# GSM.net
KiCad netlist of a schematic drawn in Altium Designer
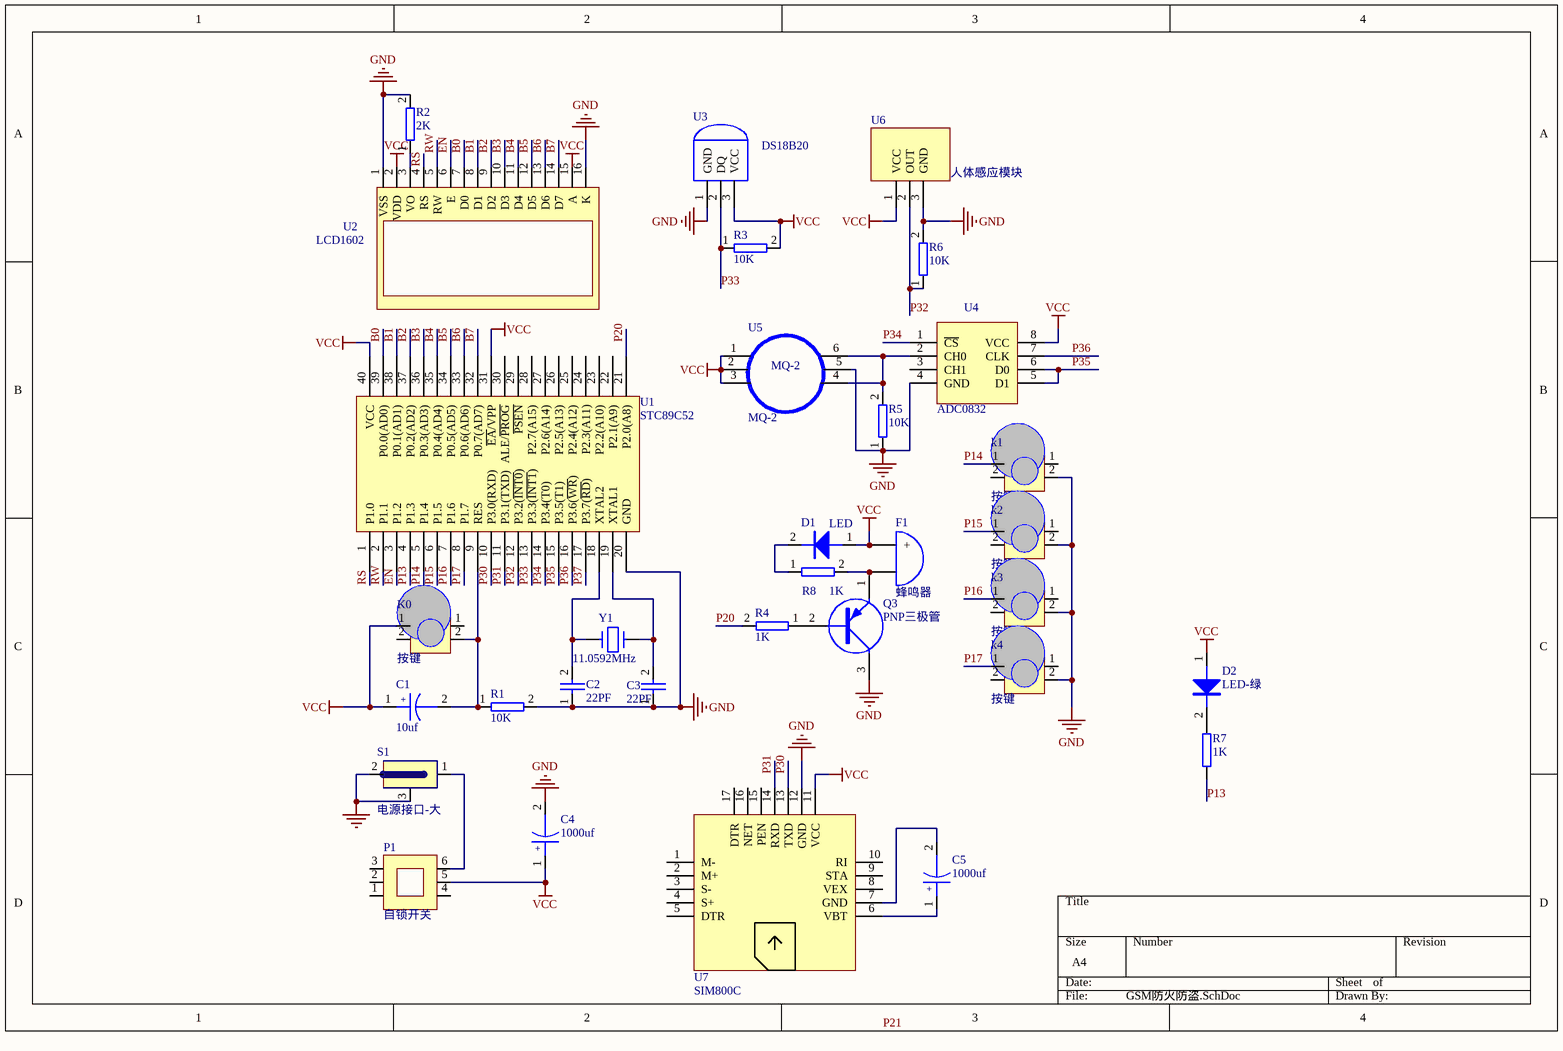
[diagram p0: GSM防火防盗.SchDoc]

(export (version "E")
  (design (tool "Eeschema 10.0.6"))
  (components
    (comp (ref "C1") (value "10uf") (footprint "电容-电解10UF") (libsource (lib "元件集成库") (part "电解电容")))
    (comp (ref "C2") (value "22PF") (footprint "电容-瓷片") (libsource (lib "元件集成库") (part "瓷片电容")))
    (comp (ref "C3") (value "22PF") (footprint "电容-瓷片") (libsource (lib "元件集成库") (part "瓷片电容")))
    (comp (ref "C4")
      (value "1000uf")
      (footprint "电容-电解1000UF - 25V")
      (libsource (lib "元件集成库") (part "电解电容-1000uf-25v"))
    )
    (comp (ref "C5")
      (value "1000uf")
      (footprint "电容-电解1000UF - 25V")
      (libsource (lib "元件集成库") (part "电解电容-1000uf-25v"))
    )
    (comp (ref "D1") (value "LED") (footprint "LED") (libsource (lib "元件集成库") (part "LED")))
    (comp (ref "D2") (value "LED-绿") (footprint "LED-5MM") (libsource (lib "元件集成库") (part "LED-5MM")))
    (comp (ref "F1") (value "蜂鸣器") (footprint "蜂鸣器") (libsource (lib "元件集成库") (part "蜂鸣器")))
    (comp (ref "K0") (value "按键") (footprint "按键") (libsource (lib "元件集成库") (part "按键")))
    (comp (ref "k1") (value "按键") (footprint "按键") (libsource (lib "元件集成库") (part "按键")))
    (comp (ref "k2") (value "按键") (footprint "按键") (libsource (lib "元件集成库") (part "按键")))
    (comp (ref "k3") (value "按键") (footprint "按键") (libsource (lib "元件集成库") (part "按键")))
    (comp (ref "k4") (value "按键") (footprint "按键") (libsource (lib "元件集成库") (part "按键")))
    (comp (ref "P1") (value "自锁开关") (footprint "自锁开关") (libsource (lib "元件集成库") (part "自锁开关")))
    (comp (ref "Q3") (value "PNP三极管") (footprint "三极管") (libsource (lib "元件集成库") (part "PNP三极管")))
    (comp (ref "R1") (value "10K") (footprint "电阻") (libsource (lib "") (part "电阻-定值_1")))
    (comp (ref "R2") (value "2K") (footprint "电阻") (libsource (lib "") (part "电阻-定值_1")))
    (comp (ref "R3") (value "10K") (footprint "电阻") (libsource (lib "") (part "电阻-定值_1")))
    (comp (ref "R4") (value "1K") (footprint "电阻") (libsource (lib "") (part "电阻-定值_1")))
    (comp (ref "R5") (value "10K") (footprint "电阻") (libsource (lib "") (part "电阻-定值_1")))
    (comp (ref "R6") (value "10K") (footprint "电阻") (libsource (lib "") (part "电阻-定值_1")))
    (comp (ref "R7") (value "1K") (footprint "电阻") (libsource (lib "元件集成库") (part "电阻-定值")))
    (comp (ref "R8") (value "1K") (footprint "电阻") (libsource (lib "") (part "电阻-定值_1")))
    (comp (ref "S1") (value "电源接口-大") (footprint "电源座-大") (libsource (lib "元件集成库") (part "电源接口-大")))
    (comp (ref "U1") (value "STC89C52") (footprint "底座40P") (libsource (lib "元件集成库") (part "STC89C52")))
    (comp (ref "U2") (value "LCD1602") (footprint "LCD1602") (libsource (lib "元件集成库") (part "LCD1602")))
    (comp (ref "U3") (value "DS18B20") (footprint "三极管") (libsource (lib "元件集成库") (part "DS18B20")))
    (comp (ref "U4") (value "ADC0832") (footprint "底座8P") (libsource (lib "元件集成库") (part "ADC0832")))
    (comp (ref "U5") (value "MQ-2") (footprint "MQ-2") (libsource (lib "元件集成库") (part "MQ-2")))
    (comp (ref "U6") (value "人体感应模块") (footprint "人体感应模块") (libsource (lib "元件集成库") (part "人体感应模块")))
    (comp (ref "U7") (value "SIM800C") (footprint "SIM800C") (libsource (lib "元件集成库") (part "SIM800C")))
    (comp (ref "Y1") (value "11.0592MHz") (footprint "晶振") (libsource (lib "元件集成库") (part "晶振")))
  )
  (nets
    (net (code "1") (name "/B0") (class "Default")
      (node (ref "U1") (pin "39") (pinfunction "P0.0(AD0)_39") (pintype "passive"))
      (node (ref "U2") (pin "7") (pinfunction "D0_7") (pintype "passive"))
    )
    (net (code "2") (name "/B1") (class "Default")
      (node (ref "U1") (pin "38") (pinfunction "P0.1(AD1)_38") (pintype "passive"))
      (node (ref "U2") (pin "8") (pinfunction "D1_8") (pintype "passive"))
    )
    (net (code "3") (name "/B2") (class "Default")
      (node (ref "U1") (pin "37") (pinfunction "P0.2(AD2)_37") (pintype "passive"))
      (node (ref "U2") (pin "9") (pinfunction "D2_9") (pintype "passive"))
    )
    (net (code "4") (name "/B3") (class "Default")
      (node (ref "U1") (pin "36") (pinfunction "P0.3(AD3)_36") (pintype "passive"))
      (node (ref "U2") (pin "10") (pinfunction "D3_10") (pintype "passive"))
    )
    (net (code "5") (name "/B4") (class "Default")
      (node (ref "U1") (pin "35") (pinfunction "P0.4(AD4)_35") (pintype "passive"))
      (node (ref "U2") (pin "11") (pinfunction "D4_11") (pintype "passive"))
    )
    (net (code "6") (name "/B5") (class "Default")
      (node (ref "U1") (pin "34") (pinfunction "P0.5(AD5)_34") (pintype "passive"))
      (node (ref "U2") (pin "12") (pinfunction "D5_12") (pintype "passive"))
    )
    (net (code "7") (name "/B6") (class "Default")
      (node (ref "U1") (pin "33") (pinfunction "P0.6(AD6)_33") (pintype "passive"))
      (node (ref "U2") (pin "13") (pinfunction "D6_13") (pintype "passive"))
    )
    (net (code "8") (name "/B7") (class "Default")
      (node (ref "U1") (pin "32") (pinfunction "P0.7(AD7)_32") (pintype "passive"))
      (node (ref "U2") (pin "14") (pinfunction "D7_14") (pintype "passive"))
    )
    (net (code "9") (name "/EN") (class "Default")
      (node (ref "U1") (pin "3") (pinfunction "P1.2_3") (pintype "passive"))
      (node (ref "U2") (pin "6") (pinfunction "E_6") (pintype "passive"))
    )
    (net (code "10") (name "/P13") (class "Default")
      (node (ref "R7") (pin "1") (pinfunction "1_1") (pintype "passive"))
      (node (ref "U1") (pin "4") (pinfunction "P1.3_4") (pintype "passive"))
    )
    (net (code "11") (name "/P14") (class "Default")
      (node (ref "U1") (pin "5") (pinfunction "P1.4_5") (pintype "passive"))
      (node (ref "k1") (pin "1") (pinfunction "1_1") (pintype "passive"))
    )
    (net (code "12") (name "/P15") (class "Default")
      (node (ref "U1") (pin "6") (pinfunction "P1.5_6") (pintype "passive"))
      (node (ref "k2") (pin "1") (pinfunction "1_1") (pintype "passive"))
    )
    (net (code "13") (name "/P16") (class "Default")
      (node (ref "U1") (pin "7") (pinfunction "P1.6_7") (pintype "passive"))
      (node (ref "k3") (pin "1") (pinfunction "1_1") (pintype "passive"))
    )
    (net (code "14") (name "/P17") (class "Default")
      (node (ref "U1") (pin "8") (pinfunction "P1.7_8") (pintype "passive"))
      (node (ref "k4") (pin "1") (pinfunction "1_1") (pintype "passive"))
    )
    (net (code "15") (name "/P20") (class "Default")
      (node (ref "R4") (pin "2") (pinfunction "2_2") (pintype "passive"))
      (node (ref "U1") (pin "21") (pinfunction "P2.0(A8)_21") (pintype "passive"))
    )
    (net (code "17") (name "/P30") (class "Default")
      (node (ref "U1") (pin "10") (pinfunction "P3.0(RXD)_10") (pintype "passive"))
      (node (ref "U7") (pin "13") (pinfunction "TXD_13") (pintype "passive"))
    )
    (net (code "18") (name "/P31") (class "Default")
      (node (ref "U1") (pin "11") (pinfunction "P3.1(TXD)_11") (pintype "passive"))
      (node (ref "U7") (pin "14") (pinfunction "RXD_14") (pintype "passive"))
    )
    (net (code "19") (name "/P32") (class "Default")
      (node (ref "R6") (pin "1") (pinfunction "1_1") (pintype "passive"))
      (node (ref "U1") (pin "12") (pinfunction "P3.2(~{INT0})_12") (pintype "passive"))
      (node (ref "U6") (pin "2") (pinfunction "OUT_2") (pintype "passive"))
    )
    (net (code "20") (name "/P33") (class "Default")
      (node (ref "R3") (pin "1") (pinfunction "1_1") (pintype "passive"))
      (node (ref "U1") (pin "13") (pinfunction "P3.3(~{INT1})_13") (pintype "passive"))
      (node (ref "U3") (pin "2") (pinfunction "DQ_2") (pintype "passive"))
    )
    (net (code "21") (name "/P34") (class "Default")
      (node (ref "U1") (pin "14") (pinfunction "P3.4(T0)_14") (pintype "passive"))
      (node (ref "U4") (pin "1") (pinfunction "~{CS}_1") (pintype "passive"))
    )
    (net (code "22") (name "/P35") (class "Default")
      (node (ref "U1") (pin "15") (pinfunction "P3.5(T1)_15") (pintype "passive"))
      (node (ref "U4") (pin "5") (pinfunction "D1_5") (pintype "passive"))
      (node (ref "U4") (pin "6") (pinfunction "D0_6") (pintype "passive"))
    )
    (net (code "23") (name "/P36") (class "Default")
      (node (ref "U1") (pin "16") (pinfunction "P3.6(~{WR})_16") (pintype "passive"))
      (node (ref "U4") (pin "7") (pinfunction "CLK_7") (pintype "passive"))
    )
    (net (code "24") (name "/P37") (class "Default")
      (node (ref "U1") (pin "17") (pinfunction "P3.7(~{RD})_17") (pintype "passive"))
    )
    (net (code "25") (name "/RS") (class "Default")
      (node (ref "U1") (pin "1") (pinfunction "P1.0_1") (pintype "passive"))
      (node (ref "U2") (pin "4") (pinfunction "RS_4") (pintype "passive"))
    )
    (net (code "26") (name "/RW") (class "Default")
      (node (ref "U1") (pin "2") (pinfunction "P1.1_2") (pintype "passive"))
      (node (ref "U2") (pin "5") (pinfunction "RW_5") (pintype "passive"))
    )
    (net (code "27") (name "GND") (class "Default")
      (node (ref "C2") (pin "1") (pinfunction "1_1") (pintype "passive"))
      (node (ref "C3") (pin "1") (pinfunction "1_1") (pintype "passive"))
      (node (ref "C4") (pin "2") (pinfunction "2_2") (pintype "passive"))
      (node (ref "Q3") (pin "3") (pinfunction "C_3") (pintype "passive"))
      (node (ref "R1") (pin "2") (pinfunction "2_2") (pintype "passive"))
      (node (ref "R2") (pin "2") (pinfunction "2_2") (pintype "passive"))
      (node (ref "R5") (pin "1") (pinfunction "1_1") (pintype "passive"))
      (node (ref "R6") (pin "2") (pinfunction "2_2") (pintype "passive"))
      (node (ref "S1") (pin "2") (pinfunction "2_2") (pintype "passive"))
      (node (ref "S1") (pin "3") (pinfunction "3_3") (pintype "passive"))
      (node (ref "U1") (pin "20") (pinfunction "GND_20") (pintype "passive"))
      (node (ref "U2") (pin "1") (pinfunction "VSS_1") (pintype "passive"))
      (node (ref "U2") (pin "16") (pinfunction "K_16") (pintype "passive"))
      (node (ref "U3") (pin "1") (pinfunction "GND_1") (pintype "passive"))
      (node (ref "U4") (pin "4") (pinfunction "GND_4") (pintype "passive"))
      (node (ref "U5") (pin "5") (pinfunction "5_5") (pintype "passive"))
      (node (ref "U6") (pin "3") (pinfunction "GND_3") (pintype "passive"))
      (node (ref "U7") (pin "12") (pinfunction "GND_12") (pintype "passive"))
      (node (ref "k1") (pin "2") (pinfunction "2_2") (pintype "passive"))
      (node (ref "k2") (pin "2") (pinfunction "2_2") (pintype "passive"))
      (node (ref "k3") (pin "2") (pinfunction "2_2") (pintype "passive"))
      (node (ref "k4") (pin "2") (pinfunction "2_2") (pintype "passive"))
    )
    (net (code "28") (name "Net-(C5-Pad2)") (class "Default")
      (node (ref "C5") (pin "2") (pinfunction "2_2") (pintype "passive"))
      (node (ref "U7") (pin "7") (pinfunction "GND_7") (pintype "passive"))
    )
    (net (code "29") (name "Net-(D1-Pad2)") (class "Default")
      (node (ref "D1") (pin "2") (pinfunction "2_2") (pintype "passive"))
      (node (ref "R8") (pin "1") (pinfunction "1_1") (pintype "passive"))
    )
    (net (code "30") (name "Net-(D2-Pad2)") (class "Default")
      (node (ref "D2") (pin "2") (pinfunction "2_2") (pintype "passive"))
      (node (ref "R7") (pin "2") (pinfunction "2_2") (pintype "passive"))
    )
    (net (code "31") (name "Net-(F1-B)") (class "Default")
      (node (ref "F1") (pin "2") (pinfunction "B_2") (pintype "passive"))
      (node (ref "Q3") (pin "1") (pinfunction "E_1") (pintype "passive"))
      (node (ref "R8") (pin "2") (pinfunction "2_2") (pintype "passive"))
    )
    (net (code "32") (name "Net-(P1-Pad6)") (class "Default")
      (node (ref "P1") (pin "6") (pinfunction "6_6") (pintype "passive"))
      (node (ref "S1") (pin "1") (pinfunction "1_1") (pintype "passive"))
    )
    (net (code "33") (name "Net-(Q3-B)") (class "Default")
      (node (ref "Q3") (pin "2") (pinfunction "B_2") (pintype "passive"))
      (node (ref "R4") (pin "1") (pinfunction "1_1") (pintype "passive"))
    )
    (net (code "34") (name "Net-(U1-RES)") (class "Default")
      (node (ref "C1") (pin "2") (pinfunction "2_2") (pintype "passive"))
      (node (ref "K0") (pin "2") (pinfunction "2_2") (pintype "passive"))
      (node (ref "R1") (pin "1") (pinfunction "1_1") (pintype "passive"))
      (node (ref "U1") (pin "9") (pinfunction "RES_9") (pintype "passive"))
    )
    (net (code "35") (name "Net-(U1-XTAL1)") (class "Default")
      (node (ref "C3") (pin "2") (pinfunction "2_2") (pintype "passive"))
      (node (ref "U1") (pin "19") (pinfunction "XTAL1_19") (pintype "passive"))
      (node (ref "Y1") (pin "2") (pinfunction "2_2") (pintype "passive"))
    )
    (net (code "36") (name "Net-(U1-XTAL2)") (class "Default")
      (node (ref "C2") (pin "2") (pinfunction "2_2") (pintype "passive"))
      (node (ref "U1") (pin "18") (pinfunction "XTAL2_18") (pintype "passive"))
      (node (ref "Y1") (pin "1") (pinfunction "1_1") (pintype "passive"))
    )
    (net (code "37") (name "Net-(U2-VO)") (class "Default")
      (node (ref "R2") (pin "1") (pinfunction "1_1") (pintype "passive"))
      (node (ref "U2") (pin "3") (pinfunction "VO_3") (pintype "passive"))
    )
    (net (code "38") (name "Net-(U4-CH0)") (class "Default")
      (node (ref "R5") (pin "2") (pinfunction "2_2") (pintype "passive"))
      (node (ref "U4") (pin "2") (pinfunction "CH0_2") (pintype "passive"))
      (node (ref "U5") (pin "4") (pinfunction "4_4") (pintype "passive"))
      (node (ref "U5") (pin "6") (pinfunction "6_6") (pintype "passive"))
    )
    (net (code "39") (name "Net-(U7-VBT)") (class "Default")
      (node (ref "C5") (pin "1") (pinfunction "1_1") (pintype "passive"))
      (node (ref "U7") (pin "6") (pinfunction "VBT_6") (pintype "passive"))
    )
    (net (code "40") (name "VCC") (class "Default")
      (node (ref "C1") (pin "1") (pinfunction "1_1") (pintype "passive"))
      (node (ref "C4") (pin "1") (pinfunction "1_1") (pintype "passive"))
      (node (ref "D1") (pin "1") (pinfunction "1_1") (pintype "passive"))
      (node (ref "D2") (pin "1") (pinfunction "1_1") (pintype "passive"))
      (node (ref "F1") (pin "1") (pinfunction "+_1") (pintype "passive"))
      (node (ref "K0") (pin "1") (pinfunction "1_1") (pintype "passive"))
      (node (ref "P1") (pin "5") (pinfunction "5_5") (pintype "passive"))
      (node (ref "R3") (pin "2") (pinfunction "2_2") (pintype "passive"))
      (node (ref "U1") (pin "31") (pinfunction "~{EA}/VPP_31") (pintype "passive"))
      (node (ref "U1") (pin "40") (pinfunction "VCC_40") (pintype "passive"))
      (node (ref "U2") (pin "15") (pinfunction "A_15") (pintype "passive"))
      (node (ref "U2") (pin "2") (pinfunction "VDD_2") (pintype "passive"))
      (node (ref "U3") (pin "3") (pinfunction "VCC_3") (pintype "passive"))
      (node (ref "U4") (pin "8") (pinfunction "VCC_8") (pintype "passive"))
      (node (ref "U5") (pin "1") (pinfunction "1_1") (pintype "passive"))
      (node (ref "U5") (pin "2") (pinfunction "2_2") (pintype "passive"))
      (node (ref "U5") (pin "3") (pinfunction "3_3") (pintype "passive"))
      (node (ref "U6") (pin "1") (pinfunction "VCC_1") (pintype "passive"))
      (node (ref "U7") (pin "11") (pinfunction "VCC_11") (pintype "passive"))
    )
    (net (code "41") (name "unconnected-(K0-Pad1)") (class "Default")
      (node (ref "K0") (pin "1") (pinfunction "1_1") (pintype "passive"))
    )
    (net (code "42") (name "unconnected-(K0-Pad2)") (class "Default")
      (node (ref "K0") (pin "2") (pinfunction "2_2") (pintype "passive"))
    )
    (net (code "43") (name "unconnected-(P1-Pad1)") (class "Default")
      (node (ref "P1") (pin "1") (pinfunction "1_1") (pintype "passive"))
    )
    (net (code "44") (name "unconnected-(P1-Pad2)") (class "Default")
      (node (ref "P1") (pin "2") (pinfunction "2_2") (pintype "passive"))
    )
    (net (code "45") (name "unconnected-(P1-Pad3)") (class "Default")
      (node (ref "P1") (pin "3") (pinfunction "3_3") (pintype "passive"))
    )
    (net (code "46") (name "unconnected-(P1-Pad4)") (class "Default")
      (node (ref "P1") (pin "4") (pinfunction "4_4") (pintype "passive"))
    )
    (net (code "47") (name "unconnected-(U1-ALE{slash}~{PROG}-Pad30)") (class "Default")
      (node (ref "U1") (pin "30") (pinfunction "ALE/~{PROG}_30") (pintype "passive"))
    )
    (net (code "48") (name "unconnected-(U1-P2.1(A9)-Pad22)") (class "Default")
      (node (ref "U1") (pin "22") (pinfunction "P2.1(A9)_22") (pintype "passive"))
    )
    (net (code "49") (name "unconnected-(U1-P2.2(A10)-Pad23)") (class "Default")
      (node (ref "U1") (pin "23") (pinfunction "P2.2(A10)_23") (pintype "passive"))
    )
    (net (code "50") (name "unconnected-(U1-P2.3(A11)-Pad24)") (class "Default")
      (node (ref "U1") (pin "24") (pinfunction "P2.3(A11)_24") (pintype "passive"))
    )
    (net (code "51") (name "unconnected-(U1-P2.4(A12)-Pad25)") (class "Default")
      (node (ref "U1") (pin "25") (pinfunction "P2.4(A12)_25") (pintype "passive"))
    )
    (net (code "52") (name "unconnected-(U1-P2.5(A13)-Pad26)") (class "Default")
      (node (ref "U1") (pin "26") (pinfunction "P2.5(A13)_26") (pintype "passive"))
    )
    (net (code "53") (name "unconnected-(U1-P2.6(A14)-Pad27)") (class "Default")
      (node (ref "U1") (pin "27") (pinfunction "P2.6(A14)_27") (pintype "passive"))
    )
    (net (code "54") (name "unconnected-(U1-P2.7(A15)-Pad28)") (class "Default")
      (node (ref "U1") (pin "28") (pinfunction "P2.7(A15)_28") (pintype "passive"))
    )
    (net (code "55") (name "unconnected-(U1-~{PSEN}-Pad29)") (class "Default")
      (node (ref "U1") (pin "29") (pinfunction "~{PSEN}_29") (pintype "passive"))
    )
    (net (code "56") (name "unconnected-(U4-CH1-Pad3)") (class "Default")
      (node (ref "U4") (pin "3") (pinfunction "CH1_3") (pintype "passive"))
    )
    (net (code "57") (name "unconnected-(U7-DTR-Pad5)") (class "Default")
      (node (ref "U7") (pin "5") (pinfunction "DTR_5") (pintype "passive"))
    )
    (net (code "58") (name "unconnected-(U7-DTR-Pad17)") (class "Default")
      (node (ref "U7") (pin "17") (pinfunction "DTR_17") (pintype "passive"))
    )
    (net (code "59") (name "unconnected-(U7-M+-Pad2)") (class "Default")
      (node (ref "U7") (pin "2") (pinfunction "M+_2") (pintype "passive"))
    )
    (net (code "60") (name "unconnected-(U7-M--Pad1)") (class "Default")
      (node (ref "U7") (pin "1") (pinfunction "M-_1") (pintype "passive"))
    )
    (net (code "61") (name "unconnected-(U7-NET-Pad16)") (class "Default")
      (node (ref "U7") (pin "16") (pinfunction "NET_16") (pintype "passive"))
    )
    (net (code "62") (name "unconnected-(U7-PEN-Pad15)") (class "Default")
      (node (ref "U7") (pin "15") (pinfunction "PEN_15") (pintype "passive"))
    )
    (net (code "63") (name "unconnected-(U7-RI-Pad10)") (class "Default")
      (node (ref "U7") (pin "10") (pinfunction "RI_10") (pintype "passive"))
    )
    (net (code "64") (name "unconnected-(U7-S+-Pad4)") (class "Default")
      (node (ref "U7") (pin "4") (pinfunction "S+_4") (pintype "passive"))
    )
    (net (code "65") (name "unconnected-(U7-S--Pad3)") (class "Default")
      (node (ref "U7") (pin "3") (pinfunction "S-_3") (pintype "passive"))
    )
    (net (code "66") (name "unconnected-(U7-STA-Pad9)") (class "Default")
      (node (ref "U7") (pin "9") (pinfunction "STA_9") (pintype "passive"))
    )
    (net (code "67") (name "unconnected-(U7-VEX-Pad8)") (class "Default")
      (node (ref "U7") (pin "8") (pinfunction "VEX_8") (pintype "passive"))
    )
    (net (code "68") (name "unconnected-(k1-Pad1)") (class "Default")
      (node (ref "k1") (pin "1") (pinfunction "1_1") (pintype "passive"))
    )
    (net (code "69") (name "unconnected-(k1-Pad2)") (class "Default")
      (node (ref "k1") (pin "2") (pinfunction "2_2") (pintype "passive"))
    )
    (net (code "70") (name "unconnected-(k2-Pad1)") (class "Default")
      (node (ref "k2") (pin "1") (pinfunction "1_1") (pintype "passive"))
    )
    (net (code "71") (name "unconnected-(k2-Pad2)") (class "Default")
      (node (ref "k2") (pin "2") (pinfunction "2_2") (pintype "passive"))
    )
    (net (code "72") (name "unconnected-(k3-Pad1)") (class "Default")
      (node (ref "k3") (pin "1") (pinfunction "1_1") (pintype "passive"))
    )
    (net (code "73") (name "unconnected-(k3-Pad2)") (class "Default")
      (node (ref "k3") (pin "2") (pinfunction "2_2") (pintype "passive"))
    )
    (net (code "74") (name "unconnected-(k4-Pad1)") (class "Default")
      (node (ref "k4") (pin "1") (pinfunction "1_1") (pintype "passive"))
    )
    (net (code "75") (name "unconnected-(k4-Pad2)") (class "Default")
      (node (ref "k4") (pin "2") (pinfunction "2_2") (pintype "passive"))
    )
  )
)
